# Sheet_Final.net
KiCad netlist of a schematic drawn in Altium Designer
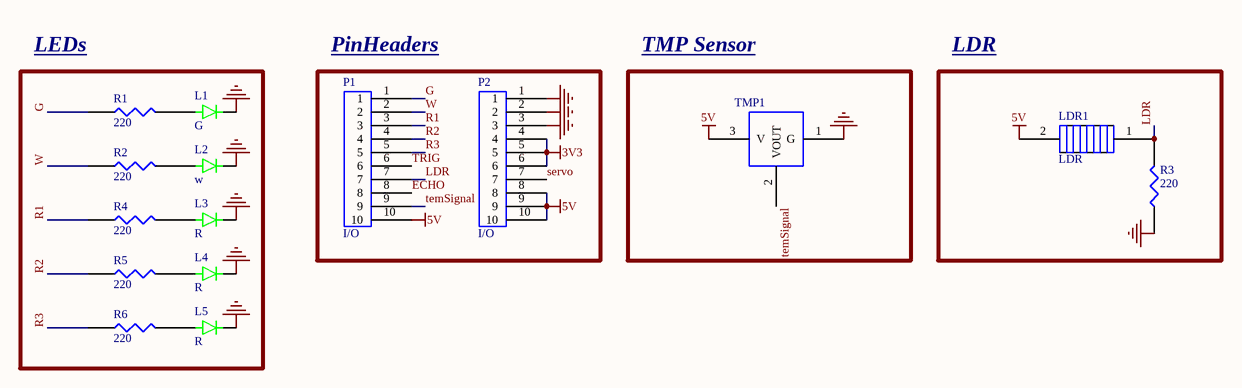
[diagram p0: Sheet_Final.SchDoc]

(export (version "E")
  (design (tool "Eeschema 10.0.6"))
  (components
    (comp (ref "L1") (value "G") (footprint "Led") (libsource (lib "Schlib1") (part "G_Led")))
    (comp (ref "L2") (value "w") (footprint "Led") (libsource (lib "Schlib1") (part "G_Led")))
    (comp (ref "L3") (value "R") (footprint "Led") (libsource (lib "Schlib1") (part "G_Led")))
    (comp (ref "L4") (value "R") (footprint "Led") (libsource (lib "Schlib1") (part "G_Led")))
    (comp (ref "L5") (value "R") (footprint "Led") (libsource (lib "Schlib1") (part "G_Led")))
    (comp (ref "LDR1")
      (value "LDR")
      (footprint "LDR")
      (description "540nm 100kΩ~200kΩ 10MΩ Through Hole,P=3mm Photoresistors ROHS")
      (fields (field (name "MANUFACTURER") "Senba Sensing Tech") (field (name "MFR. PART #") "GL5549"))
      (libsource (lib "Schlib1") (part "LDR"))
    )
    (comp (ref "P1")
      (value "I/O")
      (footprint "pin headers")
      (fields (field (name "MANUFACTURER") "XFCN") (field (name "MFR. PART #") "PZ254V-11-04P"))
      (libsource (lib "Schlib1") (part "Pin Headers"))
    )
    (comp (ref "P2")
      (value "I/O")
      (footprint "pin headers")
      (fields (field (name "MANUFACTURER") "XFCN") (field (name "MFR. PART #") "PZ254V-11-04P"))
      (libsource (lib "Schlib1") (part "Pin Headers"))
    )
    (comp (ref "R1")
      (value "220")
      (footprint "AXIAL0.3")
      (libsource (lib "Alex Training Center final") (part "RES1"))
    )
    (comp (ref "R2")
      (value "220")
      (footprint "AXIAL0.3")
      (libsource (lib "Alex Training Center final") (part "RES1"))
    )
    (comp (ref "R3")
      (value "220")
      (footprint "AXIAL0.3")
      (libsource (lib "Alex Training Center final") (part "RES1"))
    )
    (comp (ref "R4")
      (value "220")
      (footprint "AXIAL0.3")
      (libsource (lib "Alex Training Center final") (part "RES1"))
    )
    (comp (ref "R5")
      (value "220")
      (footprint "AXIAL0.3")
      (libsource (lib "Alex Training Center final") (part "RES1"))
    )
    (comp (ref "R6")
      (value "220")
      (footprint "AXIAL0.3")
      (libsource (lib "Alex Training Center final") (part "RES1"))
    )
    (comp (ref "TMP1")
      (value "LM35DZ")
      (footprint "LM35DZ")
      (description "±1.5℃ TO-92 Temperature Sensors ROHS")
      (fields (field (name "MANUFACTURER") "TI") (field (name "MFR. PART #") "LM35DZ/NOPB"))
      (libsource (lib "Schlib1") (part "LM35DZ"))
    )
  )
  (nets
    (net (code "1") (name "/ECHO") (class "Default")
      (node (ref "P1") (pin "8") (pinfunction "8_8") (pintype "passive"))
    )
    (net (code "2") (name "/G") (class "Default")
      (node (ref "P1") (pin "1") (pinfunction "1_1") (pintype "passive"))
      (node (ref "R1") (pin "1") (pinfunction "1_1") (pintype "passive"))
    )
    (net (code "3") (name "/LDR") (class "Default")
      (node (ref "LDR1") (pin "1") (pinfunction "1_1") (pintype "passive"))
      (node (ref "P1") (pin "7") (pinfunction "7_7") (pintype "passive"))
      (node (ref "R3") (pin "2") (pinfunction "2_2") (pintype "passive"))
    )
    (net (code "4") (name "/R1") (class "Default")
      (node (ref "P1") (pin "3") (pinfunction "3_3") (pintype "passive"))
      (node (ref "R4") (pin "1") (pinfunction "1_1") (pintype "passive"))
    )
    (net (code "5") (name "/R2") (class "Default")
      (node (ref "P1") (pin "4") (pinfunction "4_4") (pintype "passive"))
      (node (ref "R5") (pin "1") (pinfunction "1_1") (pintype "passive"))
    )
    (net (code "6") (name "/R3") (class "Default")
      (node (ref "P1") (pin "5") (pinfunction "5_5") (pintype "passive"))
      (node (ref "R6") (pin "1") (pinfunction "1_1") (pintype "passive"))
    )
    (net (code "7") (name "/TRIG") (class "Default")
      (node (ref "P1") (pin "6") (pinfunction "6_6") (pintype "passive"))
    )
    (net (code "8") (name "/W") (class "Default")
      (node (ref "P1") (pin "2") (pinfunction "2_2") (pintype "passive"))
      (node (ref "R2") (pin "1") (pinfunction "1_1") (pintype "passive"))
    )
    (net (code "9") (name "/servo") (class "Default")
      (node (ref "P2") (pin "7") (pinfunction "7_7") (pintype "passive"))
    )
    (net (code "10") (name "/temSignal") (class "Default")
      (node (ref "P1") (pin "9") (pinfunction "9_9") (pintype "passive"))
      (node (ref "TMP1") (pin "2") (pinfunction "VOUT_2") (pintype "passive"))
    )
    (net (code "11") (name "3V3") (class "Default")
      (node (ref "P2") (pin "4") (pinfunction "4_4") (pintype "passive"))
      (node (ref "P2") (pin "5") (pinfunction "5_5") (pintype "passive"))
      (node (ref "P2") (pin "6") (pinfunction "6_6") (pintype "passive"))
    )
    (net (code "12") (name "5V") (class "Default")
      (node (ref "LDR1") (pin "2") (pinfunction "2_2") (pintype "passive"))
      (node (ref "P1") (pin "10") (pinfunction "10_10") (pintype "passive"))
      (node (ref "P2") (pin "10") (pinfunction "10_10") (pintype "passive"))
      (node (ref "P2") (pin "8") (pinfunction "8_8") (pintype "passive"))
      (node (ref "P2") (pin "9") (pinfunction "9_9") (pintype "passive"))
      (node (ref "TMP1") (pin "3") (pinfunction "V_3") (pintype "passive"))
    )
    (net (code "13") (name "GND") (class "Default")
      (node (ref "L1") (pin "2") (pinfunction "2_2") (pintype "passive"))
      (node (ref "L2") (pin "2") (pinfunction "2_2") (pintype "passive"))
      (node (ref "L3") (pin "2") (pinfunction "2_2") (pintype "passive"))
      (node (ref "L4") (pin "2") (pinfunction "2_2") (pintype "passive"))
      (node (ref "L5") (pin "2") (pinfunction "2_2") (pintype "passive"))
      (node (ref "P2") (pin "1") (pinfunction "1_1") (pintype "passive"))
      (node (ref "P2") (pin "2") (pinfunction "2_2") (pintype "passive"))
      (node (ref "P2") (pin "3") (pinfunction "3_3") (pintype "passive"))
      (node (ref "R3") (pin "1") (pinfunction "1_1") (pintype "passive"))
      (node (ref "TMP1") (pin "1") (pinfunction "G_1") (pintype "passive"))
    )
    (net (code "14") (name "Net-(L1-Pad1)") (class "Default")
      (node (ref "L1") (pin "1") (pinfunction "1_1") (pintype "passive"))
      (node (ref "R1") (pin "2") (pinfunction "2_2") (pintype "passive"))
    )
    (net (code "15") (name "Net-(L2-Pad1)") (class "Default")
      (node (ref "L2") (pin "1") (pinfunction "1_1") (pintype "passive"))
      (node (ref "R2") (pin "2") (pinfunction "2_2") (pintype "passive"))
    )
    (net (code "16") (name "Net-(L3-Pad1)") (class "Default")
      (node (ref "L3") (pin "1") (pinfunction "1_1") (pintype "passive"))
      (node (ref "R4") (pin "2") (pinfunction "2_2") (pintype "passive"))
    )
    (net (code "17") (name "Net-(L4-Pad1)") (class "Default")
      (node (ref "L4") (pin "1") (pinfunction "1_1") (pintype "passive"))
      (node (ref "R5") (pin "2") (pinfunction "2_2") (pintype "passive"))
    )
    (net (code "18") (name "Net-(L5-Pad1)") (class "Default")
      (node (ref "L5") (pin "1") (pinfunction "1_1") (pintype "passive"))
      (node (ref "R6") (pin "2") (pinfunction "2_2") (pintype "passive"))
    )
  )
)
